# Audio.net
KiCad netlist of a schematic drawn in Altium Designer
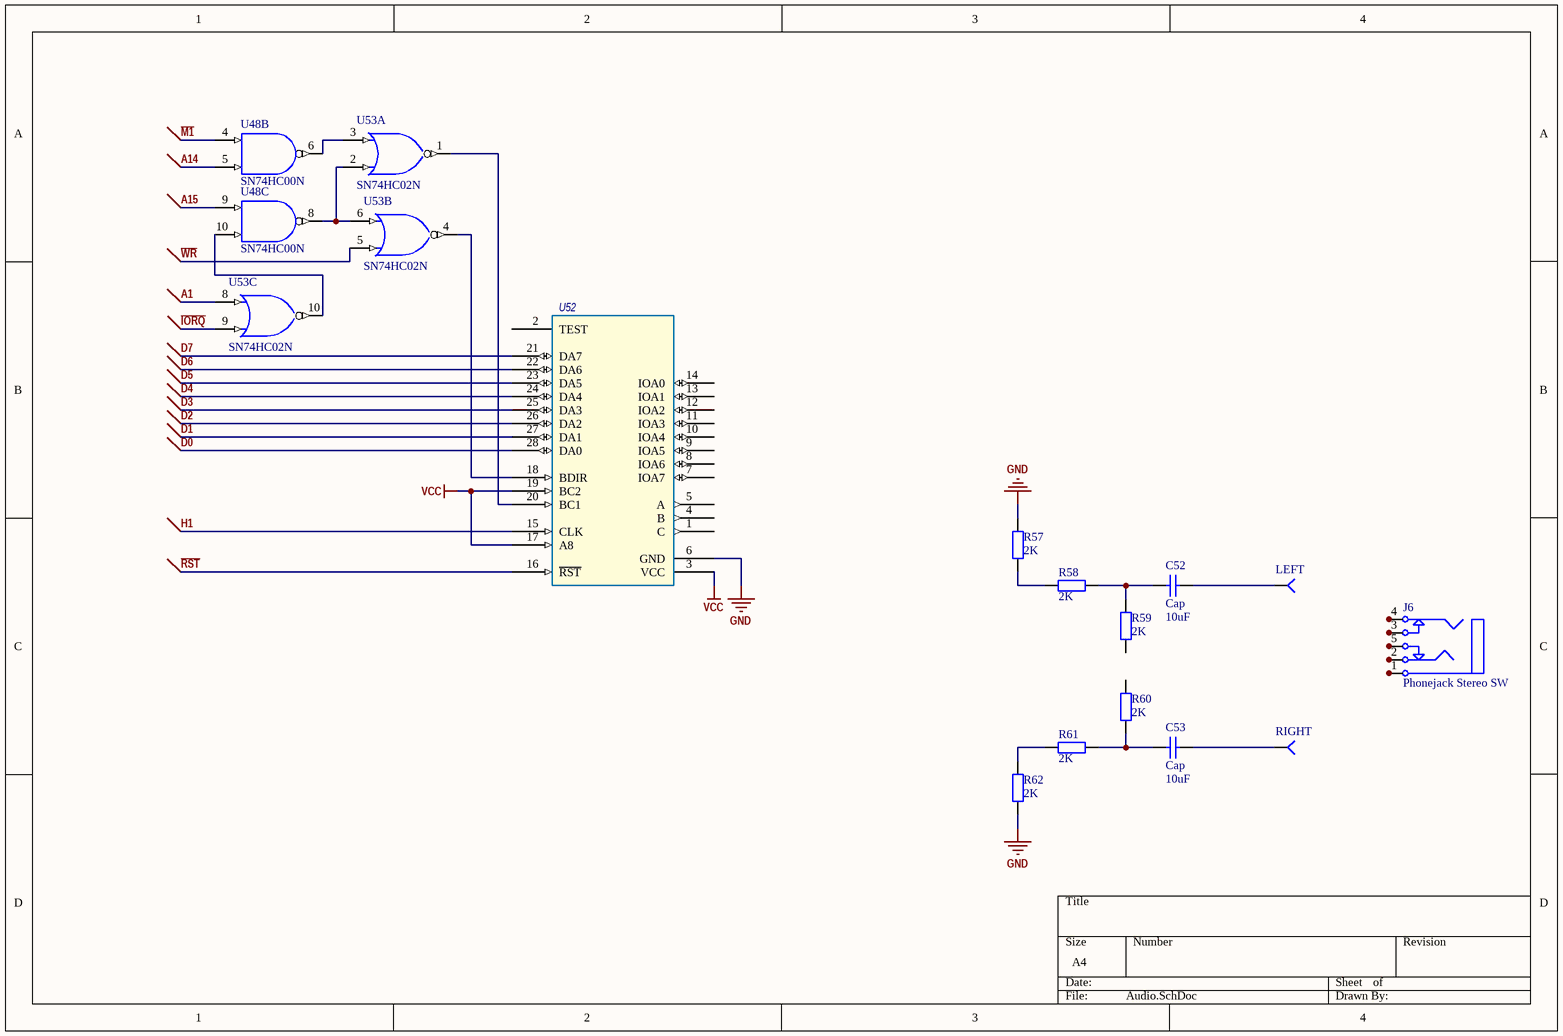
[diagram p0: Audio.SchDoc]

(export (version "E")
  (design (tool "Eeschema 10.0.6"))
  (components
    (comp (ref "C52")
      (value "Cap")
      (footprint "RAD-0.3")
      (description "Capacitor")
      (fields (field (name "ALTIUM_VALUE") "10uF") (field (name "PUBLISHER") "Altium Limited"))
      (libsource (lib "Lenin") (part "Cap"))
    )
    (comp (ref "C53")
      (value "Cap")
      (footprint "RAD-0.3")
      (description "Capacitor")
      (fields (field (name "ALTIUM_VALUE") "10uF") (field (name "PUBLISHER") "Altium Limited"))
      (libsource (lib "Lenin") (part "Cap"))
    )
    (comp (ref "J6")
      (value "Phonejack Stereo SW")
      (footprint "ST-3150-5N")
      (description "3-Conductor Jack with 2 break contacts (normals) and 2 auxiliary make contacts")
      (fields (field (name "PUBLISHER") "Altium Limited"))
      (libsource (lib "Miscellaneous Connectors") (part "Phonejack Stereo SW"))
    )
    (comp (ref "LEFT")
      (value "~")
      (footprint "PIN1")
      (description "Socket")
      (fields (field (name "PUBLISHER") "Altium Limited"))
      (libsource (lib "Lenin") (part "Socket"))
    )
    (comp (ref "R57")
      (value "2K")
      (footprint "Lenin:AXIAL-0.4")
      (description "Resistor")
      (fields (field (name "Comment") "Res2") (field (name "PUBLISHER") "Altium Limited"))
      (libsource (lib "") (part "Res2_1"))
    )
    (comp (ref "R58")
      (value "2K")
      (footprint "Lenin:AXIAL-0.4")
      (description "Resistor")
      (fields (field (name "Comment") "Res2") (field (name "PUBLISHER") "Altium Limited"))
      (libsource (lib "Lenin") (part "Res2"))
    )
    (comp (ref "R59")
      (value "2K")
      (footprint "Lenin:AXIAL-0.4")
      (description "Resistor")
      (fields (field (name "Comment") "Res2") (field (name "PUBLISHER") "Altium Limited"))
      (libsource (lib "") (part "Res2_1"))
    )
    (comp (ref "R60")
      (value "2K")
      (footprint "Lenin:AXIAL-0.4")
      (description "Resistor")
      (fields (field (name "Comment") "Res2") (field (name "PUBLISHER") "Altium Limited"))
      (libsource (lib "") (part "Res2_1"))
    )
    (comp (ref "R61")
      (value "2K")
      (footprint "Lenin:AXIAL-0.4")
      (description "Resistor")
      (fields (field (name "Comment") "Res2") (field (name "PUBLISHER") "Altium Limited"))
      (libsource (lib "Lenin") (part "Res2"))
    )
    (comp (ref "R62")
      (value "2K")
      (footprint "Lenin:AXIAL-0.4")
      (description "Resistor")
      (fields (field (name "Comment") "Res2") (field (name "PUBLISHER") "Altium Limited"))
      (libsource (lib "") (part "Res2_1"))
    )
    (comp (ref "RIGHT")
      (value "~")
      (footprint "PIN1")
      (description "Socket")
      (fields (field (name "PUBLISHER") "Altium Limited"))
      (libsource (lib "Lenin") (part "Socket"))
    )
    (comp (ref "U48")
      (value "SN74HC00N")
      (footprint "N014")
      (description "Quadruple 2-Input Positive-NAND Gate")
      (fields (field (name "PUBLISHER") "Altium Limited"))
      (libsource (lib "TI Logic Gate 2") (part "SN74HC00N"))
    )
    (comp (ref "U52")
      (value "AY-3-8912")
      (footprint "ST-Microelectronics Footprints:FDIP28W")
      (libsource (lib "Lenin") (part "AY-3-8912"))
    )
    (comp (ref "U53")
      (value "SN74HC02N")
      (footprint "N014")
      (description "Quadruple 2-Input Positive-NOR Gate")
      (fields (field (name "PUBLISHER") "Altium Limited"))
      (libsource (lib "") (part "SN74HC02N_1"))
    )
  )
  (nets
    (net (code "1") (name "/A1") (class "Default")
      (node (ref "U53") (pin "8") (pinfunction "A_8") (pintype "input"))
    )
    (net (code "2") (name "/A14") (class "Default")
      (node (ref "U48") (pin "5") (pinfunction "B_5") (pintype "input"))
    )
    (net (code "3") (name "/A15") (class "Default")
      (node (ref "U48") (pin "9") (pinfunction "A_9") (pintype "input"))
    )
    (net (code "4") (name "/D0") (class "Default")
      (node (ref "U52") (pin "28") (pinfunction "DA0_28") (pintype "bidirectional"))
    )
    (net (code "5") (name "/D1") (class "Default")
      (node (ref "U52") (pin "27") (pinfunction "DA1_27") (pintype "bidirectional"))
    )
    (net (code "6") (name "/D2") (class "Default")
      (node (ref "U52") (pin "26") (pinfunction "DA2_26") (pintype "bidirectional"))
    )
    (net (code "7") (name "/D3") (class "Default")
      (node (ref "U52") (pin "25") (pinfunction "DA3_25") (pintype "bidirectional"))
    )
    (net (code "8") (name "/D4") (class "Default")
      (node (ref "U52") (pin "24") (pinfunction "DA4_24") (pintype "bidirectional"))
    )
    (net (code "9") (name "/D5") (class "Default")
      (node (ref "U52") (pin "23") (pinfunction "DA5_23") (pintype "bidirectional"))
    )
    (net (code "10") (name "/D6") (class "Default")
      (node (ref "U52") (pin "22") (pinfunction "DA6_22") (pintype "bidirectional"))
    )
    (net (code "11") (name "/D7") (class "Default")
      (node (ref "U52") (pin "21") (pinfunction "DA7_21") (pintype "bidirectional"))
    )
    (net (code "12") (name "/H1") (class "Default")
      (node (ref "U52") (pin "15") (pinfunction "CLK_15") (pintype "input"))
    )
    (net (code "13") (name "/~{IORQ}") (class "Default")
      (node (ref "U53") (pin "9") (pinfunction "B_9") (pintype "input"))
    )
    (net (code "14") (name "/~{M1}") (class "Default")
      (node (ref "U48") (pin "4") (pinfunction "A_4") (pintype "input"))
    )
    (net (code "15") (name "/~{RST}") (class "Default")
      (node (ref "U52") (pin "16") (pinfunction "~{RST}_16") (pintype "input"))
    )
    (net (code "16") (name "/~{WR}") (class "Default")
      (node (ref "U53") (pin "5") (pinfunction "A_5") (pintype "input"))
    )
    (net (code "17") (name "GND") (class "Default")
      (node (ref "R57") (pin "2") (pinfunction "2_2") (pintype "passive"))
      (node (ref "R62") (pin "1") (pinfunction "1_1") (pintype "passive"))
      (node (ref "U48") (pin "7") (pinfunction "GND_7") (pintype "power_in"))
      (node (ref "U52") (pin "6") (pinfunction "GND_6") (pintype "power_in"))
      (node (ref "U53") (pin "7") (pinfunction "GND_7") (pintype "power_in"))
    )
    (net (code "18") (name "Net-(C52-Pad1)") (class "Default")
      (node (ref "C52") (pin "1") (pinfunction "1_1") (pintype "passive"))
      (node (ref "R58") (pin "2") (pinfunction "2_2") (pintype "passive"))
      (node (ref "R59") (pin "2") (pinfunction "2_2") (pintype "passive"))
    )
    (net (code "19") (name "Net-(C52-Pad2)") (class "Default")
      (node (ref "C52") (pin "2") (pinfunction "2_2") (pintype "passive"))
      (node (ref "LEFT") (pin "1") (pinfunction "1_1") (pintype "passive"))
    )
    (net (code "20") (name "Net-(C53-Pad1)") (class "Default")
      (node (ref "C53") (pin "1") (pinfunction "1_1") (pintype "passive"))
      (node (ref "R60") (pin "1") (pinfunction "1_1") (pintype "passive"))
      (node (ref "R61") (pin "2") (pinfunction "2_2") (pintype "passive"))
    )
    (net (code "21") (name "Net-(C53-Pad2)") (class "Default")
      (node (ref "C53") (pin "2") (pinfunction "2_2") (pintype "passive"))
      (node (ref "RIGHT") (pin "1") (pinfunction "1_1") (pintype "passive"))
    )
    (net (code "22") (name "Net-(J6-Pad1)") (class "Default")
      (node (ref "J6") (pin "1") (pinfunction "1_1") (pintype "passive"))
      (node (ref "J6") (pin "1A") (pinfunction "1A_1A") (pintype "passive"))
      (node (ref "J6") (pin "1B") (pinfunction "1B_1B") (pintype "passive"))
    )
    (net (code "23") (name "Net-(J6-Pad2)") (class "Default")
      (node (ref "J6") (pin "2") (pinfunction "2_2") (pintype "passive"))
      (node (ref "J6") (pin "2A") (pinfunction "2A_2A") (pintype "passive"))
      (node (ref "J6") (pin "2B") (pinfunction "2B_2B") (pintype "passive"))
    )
    (net (code "24") (name "Net-(J6-Pad3)") (class "Default")
      (node (ref "J6") (pin "3") (pinfunction "3_3") (pintype "passive"))
      (node (ref "J6") (pin "3A") (pinfunction "3A_3A") (pintype "passive"))
      (node (ref "J6") (pin "3B") (pinfunction "3B_3B") (pintype "passive"))
    )
    (net (code "25") (name "Net-(J6-Pad4)") (class "Default")
      (node (ref "J6") (pin "4") (pinfunction "4_4") (pintype "passive"))
      (node (ref "J6") (pin "4A") (pinfunction "4A_4A") (pintype "passive"))
      (node (ref "J6") (pin "4B") (pinfunction "4B_4B") (pintype "passive"))
    )
    (net (code "26") (name "Net-(J6-Pad5)") (class "Default")
      (node (ref "J6") (pin "5") (pinfunction "5_5") (pintype "passive"))
      (node (ref "J6") (pin "5A") (pinfunction "5A_5A") (pintype "passive"))
      (node (ref "J6") (pin "5B") (pinfunction "5B_5B") (pintype "passive"))
    )
    (net (code "27") (name "Net-(R57-Pad1)") (class "Default")
      (node (ref "R57") (pin "1") (pinfunction "1_1") (pintype "passive"))
      (node (ref "R58") (pin "1") (pinfunction "1_1") (pintype "passive"))
    )
    (net (code "28") (name "Net-(R61-Pad1)") (class "Default")
      (node (ref "R61") (pin "1") (pinfunction "1_1") (pintype "passive"))
      (node (ref "R62") (pin "2") (pinfunction "2_2") (pintype "passive"))
    )
    (net (code "29") (name "Net-(U48B-Y)") (class "Default")
      (node (ref "U48") (pin "6") (pinfunction "Y_6") (pintype "output"))
      (node (ref "U53") (pin "3") (pinfunction "B_3") (pintype "input"))
    )
    (net (code "30") (name "Net-(U48C-B)") (class "Default")
      (node (ref "U48") (pin "10") (pinfunction "B_10") (pintype "input"))
      (node (ref "U53") (pin "10") (pinfunction "Y_10") (pintype "output"))
    )
    (net (code "31") (name "Net-(U48C-Y)") (class "Default")
      (node (ref "U48") (pin "8") (pinfunction "Y_8") (pintype "output"))
      (node (ref "U53") (pin "2") (pinfunction "A_2") (pintype "input"))
      (node (ref "U53") (pin "6") (pinfunction "B_6") (pintype "input"))
    )
    (net (code "32") (name "Net-(U52-BC1)") (class "Default")
      (node (ref "U52") (pin "20") (pinfunction "BC1_20") (pintype "input"))
      (node (ref "U53") (pin "1") (pinfunction "Y_1") (pintype "output"))
    )
    (net (code "33") (name "Net-(U52-BDIR)") (class "Default")
      (node (ref "U52") (pin "18") (pinfunction "BDIR_18") (pintype "input"))
      (node (ref "U53") (pin "4") (pinfunction "Y_4") (pintype "output"))
    )
    (net (code "34") (name "VCC") (class "Default")
      (node (ref "U48") (pin "14") (pinfunction "VCC_14") (pintype "power_in"))
      (node (ref "U52") (pin "17") (pinfunction "A8_17") (pintype "input"))
      (node (ref "U52") (pin "19") (pinfunction "BC2_19") (pintype "input"))
      (node (ref "U52") (pin "3") (pinfunction "VCC_3") (pintype "power_in"))
      (node (ref "U53") (pin "14") (pinfunction "VCC_14") (pintype "power_in"))
    )
    (net (code "35") (name "unconnected-(R59-Pad1)") (class "Default")
      (node (ref "R59") (pin "1") (pinfunction "1_1") (pintype "passive"))
    )
    (net (code "36") (name "unconnected-(R60-Pad2)") (class "Default")
      (node (ref "R60") (pin "2") (pinfunction "2_2") (pintype "passive"))
    )
    (net (code "37") (name "unconnected-(U52-A-Pad5)") (class "Default")
      (node (ref "U52") (pin "5") (pinfunction "A_5") (pintype "output"))
    )
    (net (code "38") (name "unconnected-(U52-B-Pad4)") (class "Default")
      (node (ref "U52") (pin "4") (pinfunction "B_4") (pintype "output"))
    )
    (net (code "39") (name "unconnected-(U52-C-Pad1)") (class "Default")
      (node (ref "U52") (pin "1") (pinfunction "C_1") (pintype "output"))
    )
    (net (code "40") (name "unconnected-(U52-IOA0-Pad14)") (class "Default")
      (node (ref "U52") (pin "14") (pinfunction "IOA0_14") (pintype "bidirectional"))
    )
    (net (code "41") (name "unconnected-(U52-IOA1-Pad13)") (class "Default")
      (node (ref "U52") (pin "13") (pinfunction "IOA1_13") (pintype "bidirectional"))
    )
    (net (code "42") (name "unconnected-(U52-IOA2-Pad12)") (class "Default")
      (node (ref "U52") (pin "12") (pinfunction "IOA2_12") (pintype "bidirectional"))
    )
    (net (code "43") (name "unconnected-(U52-IOA3-Pad11)") (class "Default")
      (node (ref "U52") (pin "11") (pinfunction "IOA3_11") (pintype "bidirectional"))
    )
    (net (code "44") (name "unconnected-(U52-IOA4-Pad10)") (class "Default")
      (node (ref "U52") (pin "10") (pinfunction "IOA4_10") (pintype "bidirectional"))
    )
    (net (code "45") (name "unconnected-(U52-IOA5-Pad9)") (class "Default")
      (node (ref "U52") (pin "9") (pinfunction "IOA5_9") (pintype "bidirectional"))
    )
    (net (code "46") (name "unconnected-(U52-IOA6-Pad8)") (class "Default")
      (node (ref "U52") (pin "8") (pinfunction "IOA6_8") (pintype "bidirectional"))
    )
    (net (code "47") (name "unconnected-(U52-IOA7-Pad7)") (class "Default")
      (node (ref "U52") (pin "7") (pinfunction "IOA7_7") (pintype "bidirectional"))
    )
    (net (code "48") (name "unconnected-(U52-TEST-Pad2)") (class "Default")
      (node (ref "U52") (pin "2") (pinfunction "TEST_2") (pintype "passive"))
    )
  )
)
